# SCH_USB-HUB_2024-10-05.net
KiCad netlist of a schematic drawn in EasyEDA
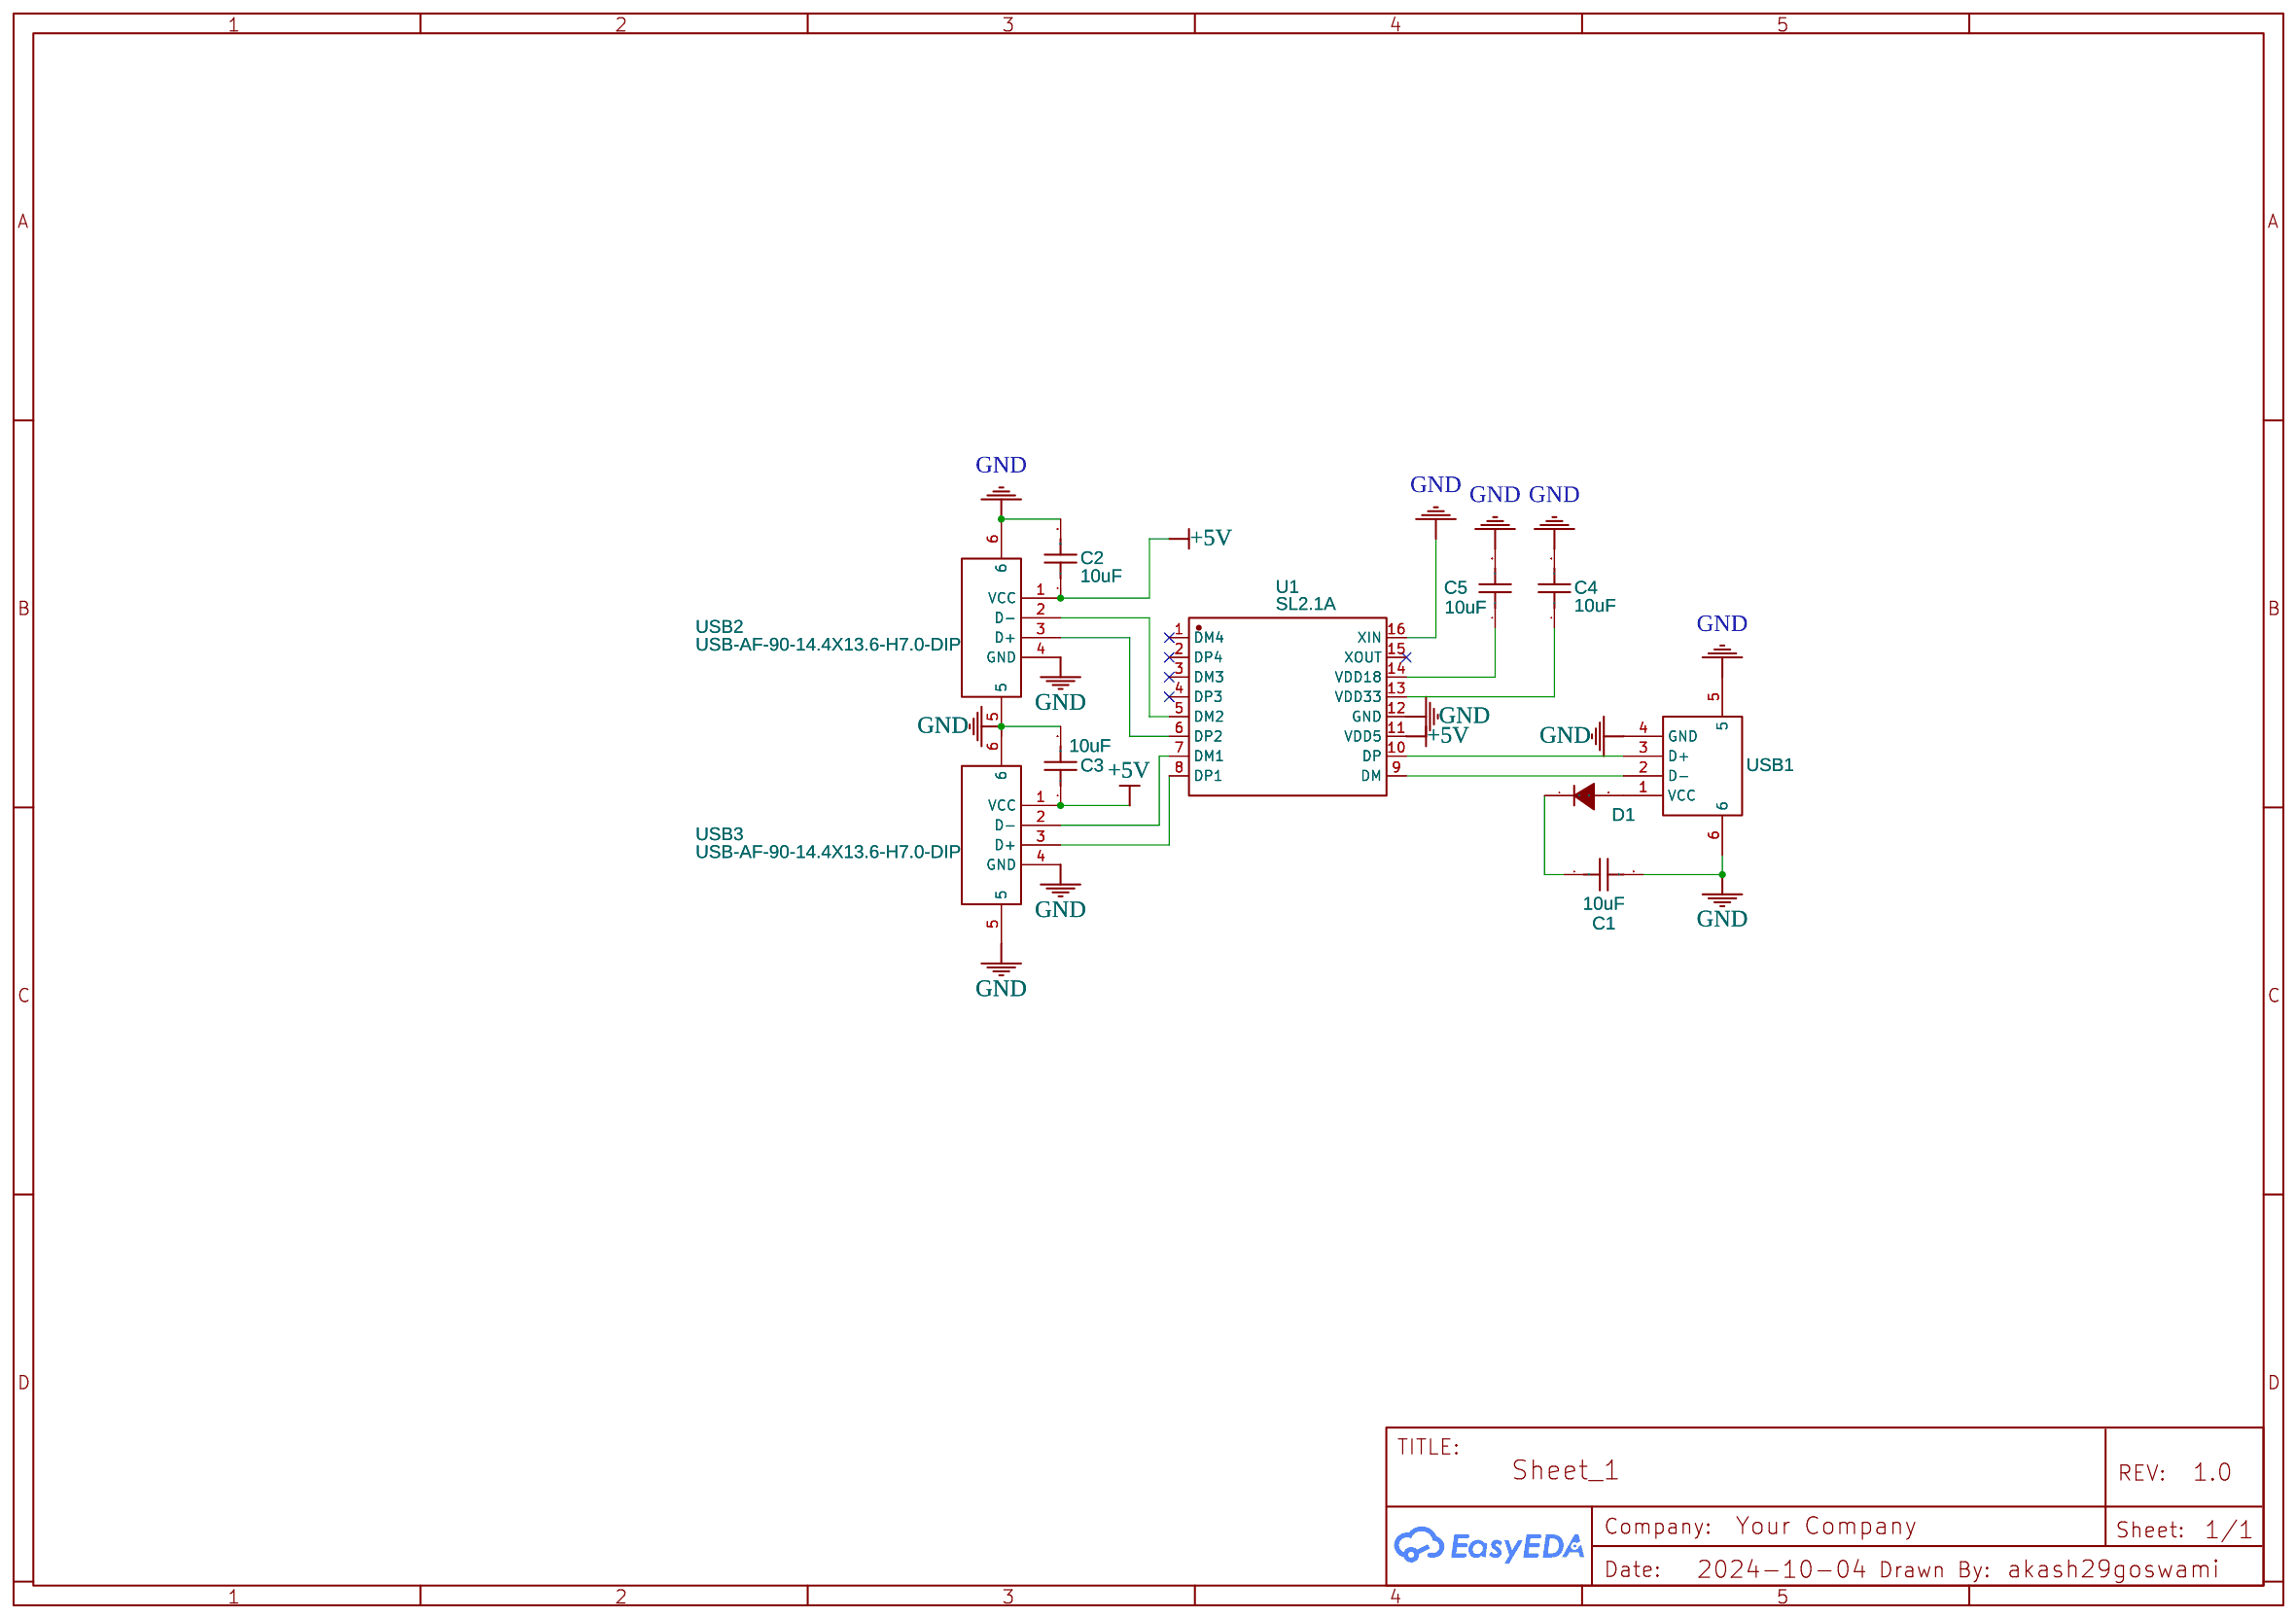
[diagram p0: schematic sheet]

(export (version "E")
  (design (tool "Eeschema 10.0.6"))
  (components
    (comp (ref "C1")
      (value "10uF")
      (fields
        (field (name "Manufacturer Part") "CL10A106KP8NNNC")
        (field (name "Manufacturer") "SAMSUNG(三星)")
      )
      (libsource (lib "") (part "CL10A106KP8NNNC_1"))
    )
    (comp (ref "C2")
      (value "10uF")
      (fields
        (field (name "Manufacturer Part") "CL10A106KP8NNNC")
        (field (name "Manufacturer") "SAMSUNG(三星)")
      )
      (libsource (lib "") (part "CL10A106KP8NNNC"))
    )
    (comp (ref "C3")
      (value "10uF")
      (fields
        (field (name "Manufacturer Part") "CL10A106KP8NNNC")
        (field (name "Manufacturer") "SAMSUNG(三星)")
      )
      (libsource (lib "") (part "CL10A106KP8NNNC"))
    )
    (comp (ref "C4")
      (value "10uF")
      (fields
        (field (name "Manufacturer Part") "CL10A106KP8NNNC")
        (field (name "Manufacturer") "SAMSUNG(三星)")
      )
      (libsource (lib "") (part "CL10A106KP8NNNC"))
    )
    (comp (ref "C5")
      (value "10uF")
      (fields
        (field (name "Manufacturer Part") "CL10A106KP8NNNC")
        (field (name "Manufacturer") "SAMSUNG(三星)")
      )
      (libsource (lib "") (part "CL10A106KP8NNNC"))
    )
    (comp (ref "D1")
      (value "NSR0320MW2T1G")
      (fields (field (name "Manufacturer") "onsemi(安森美)"))
      (libsource (lib "") (part "NSR0320MW2T1G"))
    )
    (comp (ref "U1")
      (value "SL2.1A")
      (fields (field (name "Manufacturer") "CoreChips(和芯润德)"))
      (libsource (lib "") (part "SL2.1A"))
    )
    (comp (ref "USB1")
      (value "U-G-04DD-W-01")
      (fields (field (name "Manufacturer Part") "U-G-O4DD-W-1") (field (name "Manufacturer") "韩国韩荣"))
      (libsource (lib "") (part "U-G-04DD-W-01"))
    )
    (comp (ref "USB2")
      (value "USB-AF-90-14.4X13.6-H7.0-DIP")
      (fields (field (name "Manufacturer Part") "903-131A1011D10100") (field (name "Manufacturer") "精拓金"))
      (libsource (lib "") (part "USB-AF-90-14.4X13.6-H7.0-DIP"))
    )
    (comp (ref "USB3")
      (value "USB-AF-90-14.4X13.6-H7.0-DIP")
      (fields (field (name "Manufacturer Part") "903-131A1011D10100") (field (name "Manufacturer") "精拓金"))
      (libsource (lib "") (part "USB-AF-90-14.4X13.6-H7.0-DIP"))
    )
  )
  (nets
    (net (code "1") (name "+5V") (class "Default")
      (node (ref "C2") (pin "1") (pinfunction "1_1") (pintype "unspecified"))
      (node (ref "C3") (pin "1") (pinfunction "1_1") (pintype "unspecified"))
      (node (ref "U1") (pin "11") (pinfunction "VDD5_11") (pintype "unspecified"))
      (node (ref "USB2") (pin "1") (pinfunction "VCC_1") (pintype "unspecified"))
      (node (ref "USB3") (pin "1") (pinfunction "VCC_1") (pintype "unspecified"))
    )
    (net (code "2") (name "GND") (class "Default")
      (node (ref "C1") (pin "2") (pinfunction "2_2") (pintype "unspecified"))
      (node (ref "C2") (pin "2") (pinfunction "2_2") (pintype "unspecified"))
      (node (ref "C3") (pin "2") (pinfunction "2_2") (pintype "unspecified"))
      (node (ref "C4") (pin "2") (pinfunction "2_2") (pintype "unspecified"))
      (node (ref "C5") (pin "2") (pinfunction "2_2") (pintype "unspecified"))
      (node (ref "U1") (pin "12") (pinfunction "GND_12") (pintype "unspecified"))
      (node (ref "U1") (pin "16") (pinfunction "XIN_16") (pintype "unspecified"))
      (node (ref "USB1") (pin "4") (pinfunction "GND_4") (pintype "unspecified"))
      (node (ref "USB1") (pin "5") (pinfunction "5_5") (pintype "unspecified"))
      (node (ref "USB1") (pin "6") (pinfunction "6_6") (pintype "unspecified"))
      (node (ref "USB2") (pin "4") (pinfunction "GND_4") (pintype "unspecified"))
      (node (ref "USB2") (pin "6") (pinfunction "6_6") (pintype "unspecified"))
      (node (ref "USB3") (pin "4") (pinfunction "GND_4") (pintype "unspecified"))
      (node (ref "USB3") (pin "5") (pinfunction "5_5") (pintype "unspecified"))
      (node (ref "USB3") (pin "6") (pinfunction "6_6") (pintype "unspecified"))
    )
    (net (code "3") (name "Net-(D1-A)") (class "Default")
      (node (ref "D1") (pin "2") (pinfunction "A_2") (pintype "unspecified"))
      (node (ref "USB1") (pin "1") (pinfunction "VCC_1") (pintype "unspecified"))
    )
    (net (code "4") (name "Net-(D1-C)") (class "Default")
      (node (ref "C1") (pin "1") (pinfunction "1_1") (pintype "unspecified"))
      (node (ref "D1") (pin "1") (pinfunction "C_1") (pintype "unspecified"))
    )
    (net (code "5") (name "Net-(U1-DM)") (class "Default")
      (node (ref "U1") (pin "9") (pinfunction "DM_9") (pintype "unspecified"))
      (node (ref "USB1") (pin "2") (pinfunction "D-_2") (pintype "unspecified"))
    )
    (net (code "6") (name "Net-(U1-DM1)") (class "Default")
      (node (ref "U1") (pin "7") (pinfunction "DM1_7") (pintype "unspecified"))
      (node (ref "USB3") (pin "2") (pinfunction "D-_2") (pintype "unspecified"))
    )
    (net (code "7") (name "Net-(U1-DM2)") (class "Default")
      (node (ref "U1") (pin "5") (pinfunction "DM2_5") (pintype "unspecified"))
      (node (ref "USB2") (pin "2") (pinfunction "D-_2") (pintype "unspecified"))
    )
    (net (code "8") (name "Net-(U1-DP)") (class "Default")
      (node (ref "U1") (pin "10") (pinfunction "DP_10") (pintype "unspecified"))
      (node (ref "USB1") (pin "3") (pinfunction "D+_3") (pintype "unspecified"))
    )
    (net (code "9") (name "Net-(U1-DP1)") (class "Default")
      (node (ref "U1") (pin "8") (pinfunction "DP1_8") (pintype "unspecified"))
      (node (ref "USB3") (pin "3") (pinfunction "D+_3") (pintype "unspecified"))
    )
    (net (code "10") (name "Net-(U1-DP2)") (class "Default")
      (node (ref "U1") (pin "6") (pinfunction "DP2_6") (pintype "unspecified"))
      (node (ref "USB2") (pin "3") (pinfunction "D+_3") (pintype "unspecified"))
    )
    (net (code "11") (name "Net-(U1-VDD18)") (class "Default")
      (node (ref "C5") (pin "1") (pinfunction "1_1") (pintype "unspecified"))
      (node (ref "U1") (pin "14") (pinfunction "VDD18_14") (pintype "unspecified"))
    )
    (net (code "12") (name "Net-(U1-VDD33)") (class "Default")
      (node (ref "C4") (pin "1") (pinfunction "1_1") (pintype "unspecified"))
      (node (ref "U1") (pin "13") (pinfunction "VDD33_13") (pintype "unspecified"))
    )
    (net (code "13") (name "unconnected-(U1-DM3-Pad3)") (class "Default")
      (node (ref "U1") (pin "3") (pinfunction "DM3_3") (pintype "unspecified+no_connect"))
    )
    (net (code "14") (name "unconnected-(U1-DM4-Pad1)") (class "Default")
      (node (ref "U1") (pin "1") (pinfunction "DM4_1") (pintype "unspecified+no_connect"))
    )
    (net (code "15") (name "unconnected-(U1-DP3-Pad4)") (class "Default")
      (node (ref "U1") (pin "4") (pinfunction "DP3_4") (pintype "unspecified+no_connect"))
    )
    (net (code "16") (name "unconnected-(U1-DP4-Pad2)") (class "Default")
      (node (ref "U1") (pin "2") (pinfunction "DP4_2") (pintype "unspecified+no_connect"))
    )
    (net (code "17") (name "unconnected-(U1-XOUT-Pad15)") (class "Default")
      (node (ref "U1") (pin "15") (pinfunction "XOUT_15") (pintype "unspecified+no_connect"))
    )
    (net (code "18") (name "unconnected-(USB2-Pad5)") (class "Default")
      (node (ref "USB2") (pin "5") (pinfunction "5_5") (pintype "unspecified"))
    )
  )
)
